# Front_Board_v6.net
KiCad netlist of a schematic drawn in EAGLE
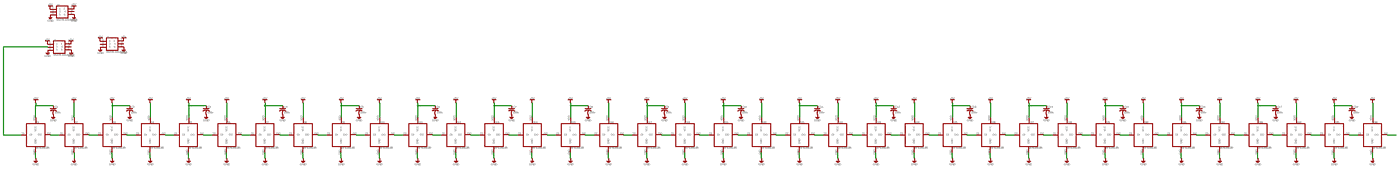
[diagram p0: schematic, sheet 1, overview]
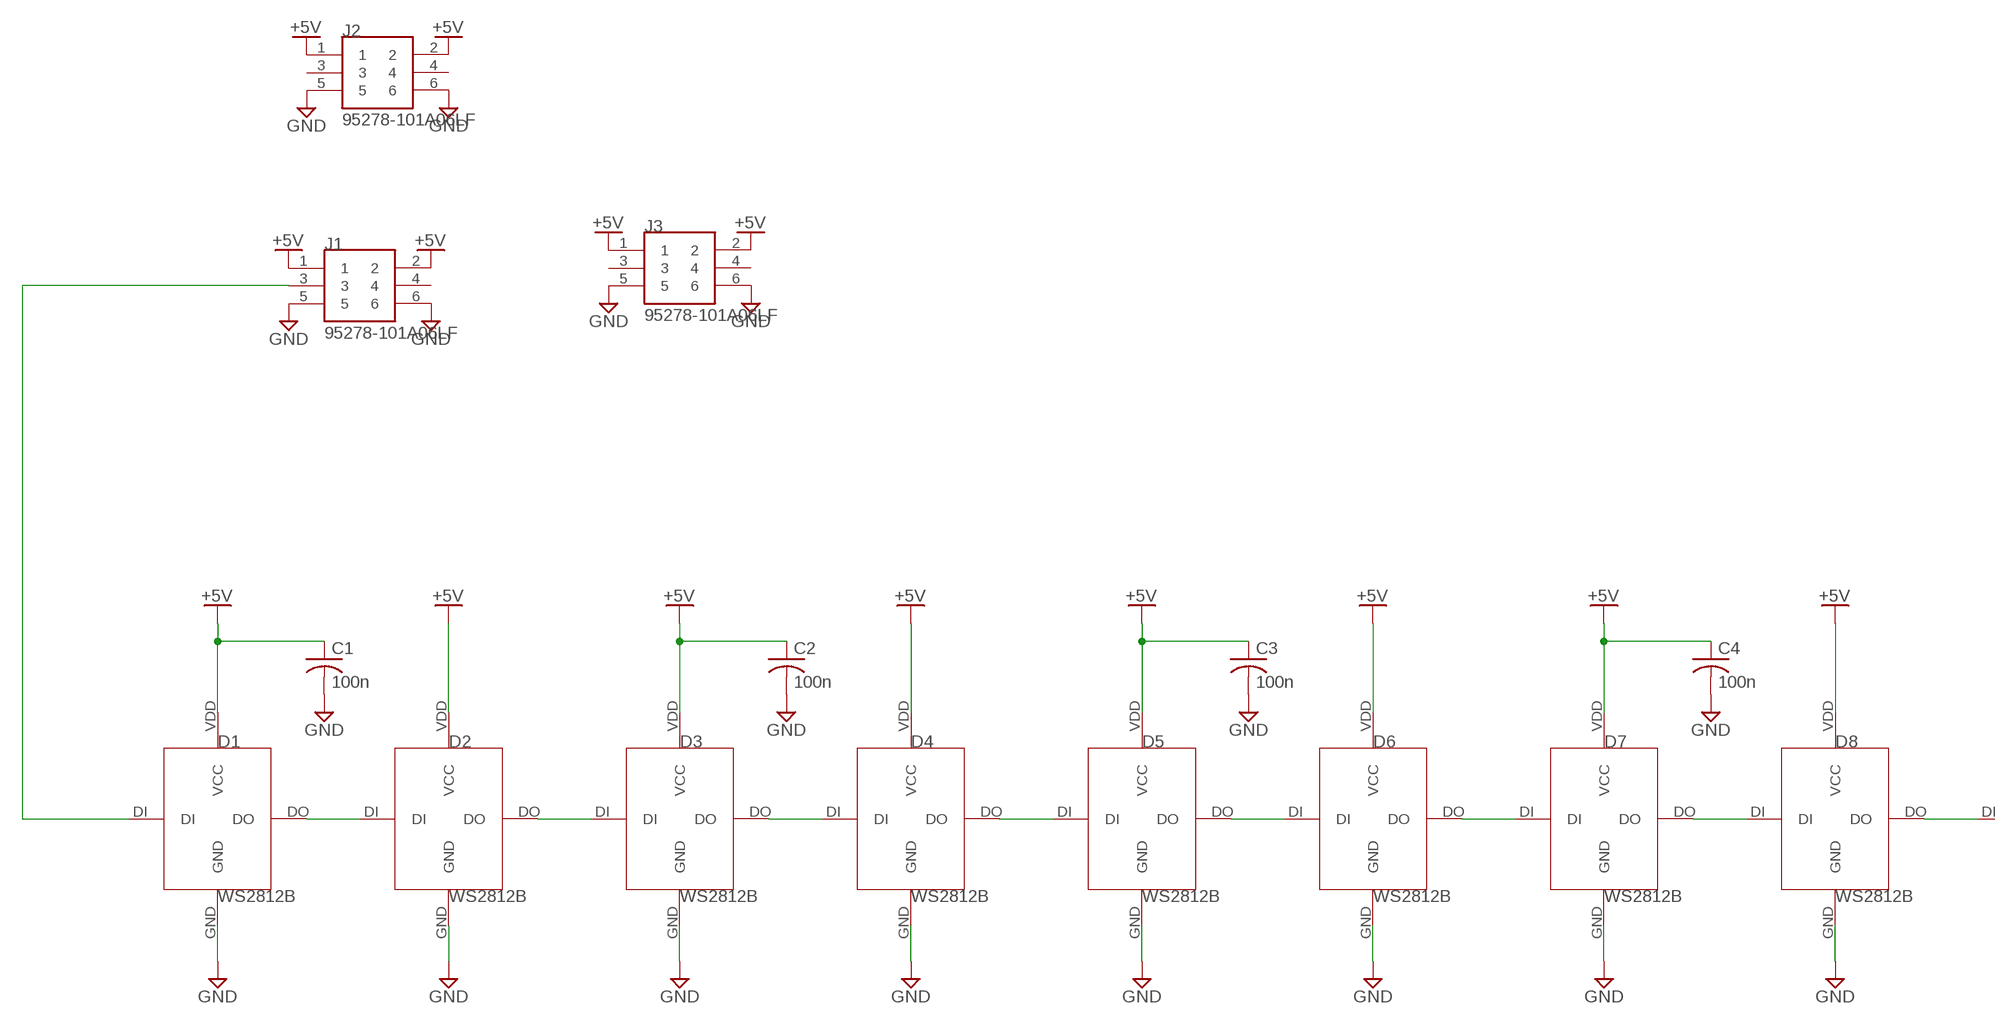
[diagram p1: schematic, sheet 1, part 1 of 4]
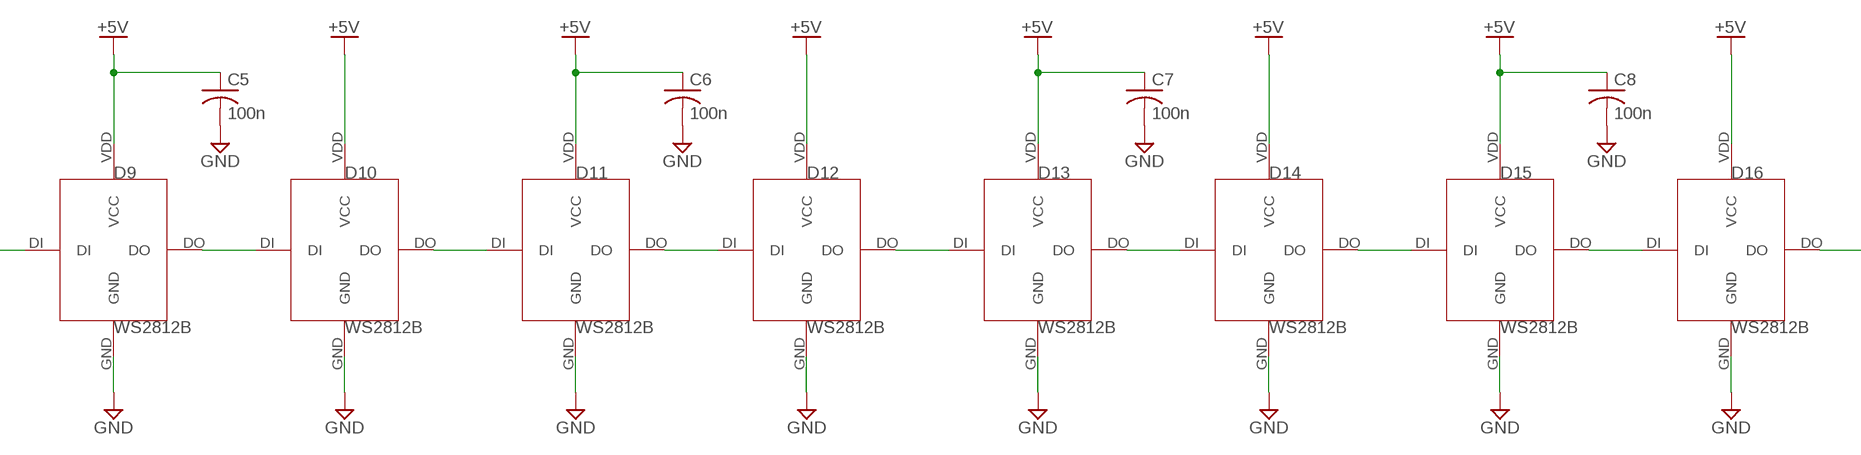
[diagram p2: schematic, sheet 1, part 2 of 4]
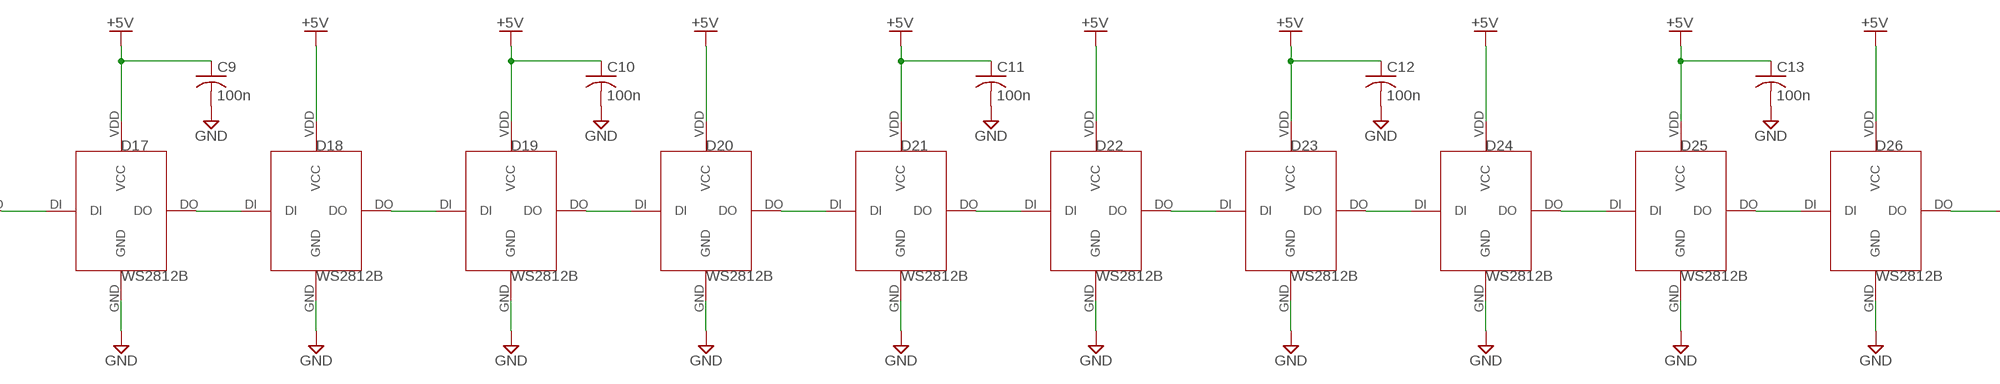
[diagram p3: schematic, sheet 1, part 3 of 4]
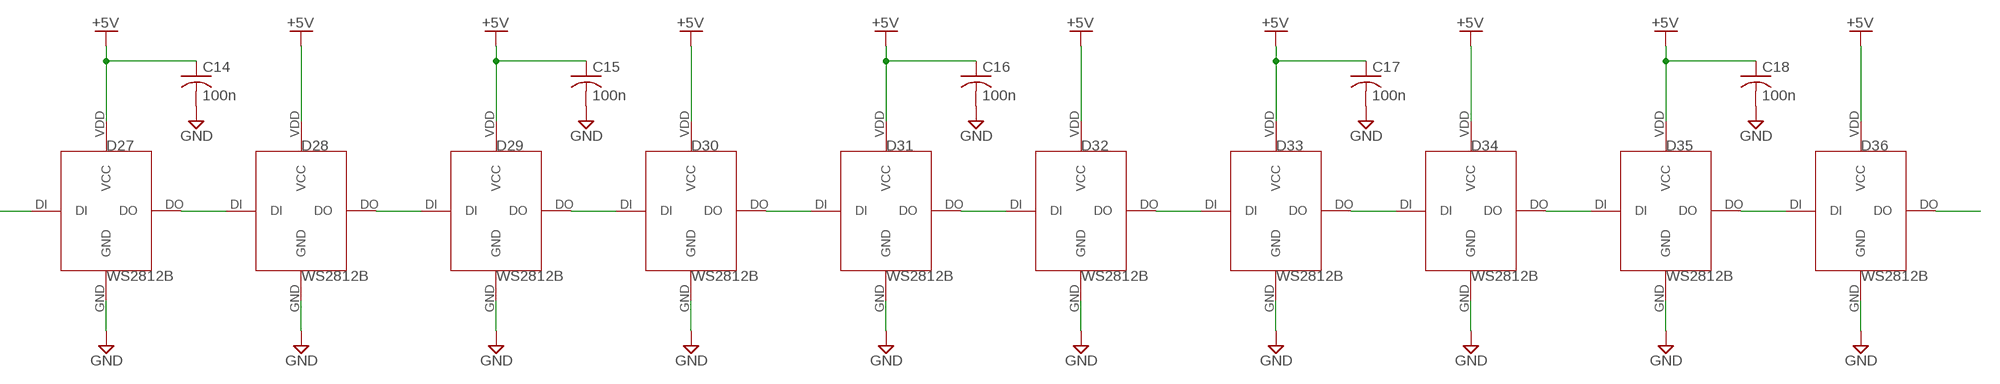
[diagram p4: schematic, sheet 1, part 4 of 4]

(export (version "E")
  (design (tool "Eeschema 10.0.6"))
  (components
    (comp (ref "C1")
      (value "100n")
      (footprint "eagle-import:C0603K")
      (libsource (lib "eagle-import") (part "C-USC0603K"))
    )
    (comp (ref "C2")
      (value "100n")
      (footprint "eagle-import:C0603K")
      (libsource (lib "eagle-import") (part "C-USC0603K"))
    )
    (comp (ref "C3")
      (value "100n")
      (footprint "eagle-import:C0603K")
      (libsource (lib "eagle-import") (part "C-USC0603K"))
    )
    (comp (ref "C4")
      (value "100n")
      (footprint "eagle-import:C0603K")
      (libsource (lib "eagle-import") (part "C-USC0603K"))
    )
    (comp (ref "C5")
      (value "100n")
      (footprint "eagle-import:C0603K")
      (libsource (lib "eagle-import") (part "C-USC0603K"))
    )
    (comp (ref "C6")
      (value "100n")
      (footprint "eagle-import:C0603K")
      (libsource (lib "eagle-import") (part "C-USC0603K"))
    )
    (comp (ref "C7")
      (value "100n")
      (footprint "eagle-import:C0603K")
      (libsource (lib "eagle-import") (part "C-USC0603K"))
    )
    (comp (ref "C8")
      (value "100n")
      (footprint "eagle-import:C0603K")
      (libsource (lib "eagle-import") (part "C-USC0603K"))
    )
    (comp (ref "C9")
      (value "100n")
      (footprint "eagle-import:C0603K")
      (libsource (lib "eagle-import") (part "C-USC0603K"))
    )
    (comp (ref "C10")
      (value "100n")
      (footprint "eagle-import:C0603K")
      (libsource (lib "eagle-import") (part "C-USC0603K"))
    )
    (comp (ref "C11")
      (value "100n")
      (footprint "eagle-import:C0603K")
      (libsource (lib "eagle-import") (part "C-USC0603K"))
    )
    (comp (ref "C12")
      (value "100n")
      (footprint "eagle-import:C0603K")
      (libsource (lib "eagle-import") (part "C-USC0603K"))
    )
    (comp (ref "C13")
      (value "100n")
      (footprint "eagle-import:C0603K")
      (libsource (lib "eagle-import") (part "C-USC0603K"))
    )
    (comp (ref "C14")
      (value "100n")
      (footprint "eagle-import:C0603K")
      (libsource (lib "eagle-import") (part "C-USC0603K"))
    )
    (comp (ref "C15")
      (value "100n")
      (footprint "eagle-import:C0603K")
      (libsource (lib "eagle-import") (part "C-USC0603K"))
    )
    (comp (ref "C16")
      (value "100n")
      (footprint "eagle-import:C0603K")
      (libsource (lib "eagle-import") (part "C-USC0603K"))
    )
    (comp (ref "C17")
      (value "100n")
      (footprint "eagle-import:C0603K")
      (libsource (lib "eagle-import") (part "C-USC0603K"))
    )
    (comp (ref "C18")
      (value "100n")
      (footprint "eagle-import:C0603K")
      (libsource (lib "eagle-import") (part "C-USC0603K"))
    )
    (comp (ref "D1")
      (value "WS2812B")
      (footprint "eagle-import:1010")
      (libsource (lib "eagle-import") (part "WS2812B"))
    )
    (comp (ref "D2")
      (value "WS2812B")
      (footprint "eagle-import:1010")
      (libsource (lib "eagle-import") (part "WS2812B"))
    )
    (comp (ref "D3")
      (value "WS2812B")
      (footprint "eagle-import:1010")
      (libsource (lib "eagle-import") (part "WS2812B"))
    )
    (comp (ref "D4")
      (value "WS2812B")
      (footprint "eagle-import:1010")
      (libsource (lib "eagle-import") (part "WS2812B"))
    )
    (comp (ref "D5")
      (value "WS2812B")
      (footprint "eagle-import:1010")
      (libsource (lib "eagle-import") (part "WS2812B"))
    )
    (comp (ref "D6")
      (value "WS2812B")
      (footprint "eagle-import:1010")
      (libsource (lib "eagle-import") (part "WS2812B"))
    )
    (comp (ref "D7")
      (value "WS2812B")
      (footprint "eagle-import:1010")
      (libsource (lib "eagle-import") (part "WS2812B"))
    )
    (comp (ref "D8")
      (value "WS2812B")
      (footprint "eagle-import:1010")
      (libsource (lib "eagle-import") (part "WS2812B"))
    )
    (comp (ref "D9")
      (value "WS2812B")
      (footprint "eagle-import:1010")
      (libsource (lib "eagle-import") (part "WS2812B"))
    )
    (comp (ref "D10")
      (value "WS2812B")
      (footprint "eagle-import:1010")
      (libsource (lib "eagle-import") (part "WS2812B"))
    )
    (comp (ref "D11")
      (value "WS2812B")
      (footprint "eagle-import:1010")
      (libsource (lib "eagle-import") (part "WS2812B"))
    )
    (comp (ref "D12")
      (value "WS2812B")
      (footprint "eagle-import:1010")
      (libsource (lib "eagle-import") (part "WS2812B"))
    )
    (comp (ref "D13")
      (value "WS2812B")
      (footprint "eagle-import:1010")
      (libsource (lib "eagle-import") (part "WS2812B"))
    )
    (comp (ref "D14")
      (value "WS2812B")
      (footprint "eagle-import:1010")
      (libsource (lib "eagle-import") (part "WS2812B"))
    )
    (comp (ref "D15")
      (value "WS2812B")
      (footprint "eagle-import:1010")
      (libsource (lib "eagle-import") (part "WS2812B"))
    )
    (comp (ref "D16")
      (value "WS2812B")
      (footprint "eagle-import:1010")
      (libsource (lib "eagle-import") (part "WS2812B"))
    )
    (comp (ref "D17")
      (value "WS2812B")
      (footprint "eagle-import:1010")
      (libsource (lib "eagle-import") (part "WS2812B"))
    )
    (comp (ref "D18")
      (value "WS2812B")
      (footprint "eagle-import:1010")
      (libsource (lib "eagle-import") (part "WS2812B"))
    )
    (comp (ref "D19")
      (value "WS2812B")
      (footprint "eagle-import:1010")
      (libsource (lib "eagle-import") (part "WS2812B"))
    )
    (comp (ref "D20")
      (value "WS2812B")
      (footprint "eagle-import:1010")
      (libsource (lib "eagle-import") (part "WS2812B"))
    )
    (comp (ref "D21")
      (value "WS2812B")
      (footprint "eagle-import:1010")
      (libsource (lib "eagle-import") (part "WS2812B"))
    )
    (comp (ref "D22")
      (value "WS2812B")
      (footprint "eagle-import:1010")
      (libsource (lib "eagle-import") (part "WS2812B"))
    )
    (comp (ref "D23")
      (value "WS2812B")
      (footprint "eagle-import:1010")
      (libsource (lib "eagle-import") (part "WS2812B"))
    )
    (comp (ref "D24")
      (value "WS2812B")
      (footprint "eagle-import:1010")
      (libsource (lib "eagle-import") (part "WS2812B"))
    )
    (comp (ref "D25")
      (value "WS2812B")
      (footprint "eagle-import:1010")
      (libsource (lib "eagle-import") (part "WS2812B"))
    )
    (comp (ref "D26")
      (value "WS2812B")
      (footprint "eagle-import:1010")
      (libsource (lib "eagle-import") (part "WS2812B"))
    )
    (comp (ref "D27")
      (value "WS2812B")
      (footprint "eagle-import:1010")
      (libsource (lib "eagle-import") (part "WS2812B"))
    )
    (comp (ref "D28")
      (value "WS2812B")
      (footprint "eagle-import:1010")
      (libsource (lib "eagle-import") (part "WS2812B"))
    )
    (comp (ref "D29")
      (value "WS2812B")
      (footprint "eagle-import:1010")
      (libsource (lib "eagle-import") (part "WS2812B"))
    )
    (comp (ref "D30")
      (value "WS2812B")
      (footprint "eagle-import:1010")
      (libsource (lib "eagle-import") (part "WS2812B"))
    )
    (comp (ref "D31")
      (value "WS2812B")
      (footprint "eagle-import:1010")
      (libsource (lib "eagle-import") (part "WS2812B"))
    )
    (comp (ref "D32")
      (value "WS2812B")
      (footprint "eagle-import:1010")
      (libsource (lib "eagle-import") (part "WS2812B"))
    )
    (comp (ref "D33")
      (value "WS2812B")
      (footprint "eagle-import:1010")
      (libsource (lib "eagle-import") (part "WS2812B"))
    )
    (comp (ref "D34")
      (value "WS2812B")
      (footprint "eagle-import:1010")
      (libsource (lib "eagle-import") (part "WS2812B"))
    )
    (comp (ref "D35")
      (value "WS2812B")
      (footprint "eagle-import:1010")
      (libsource (lib "eagle-import") (part "WS2812B"))
    )
    (comp (ref "D36")
      (value "WS2812B")
      (footprint "eagle-import:1010")
      (libsource (lib "eagle-import") (part "WS2812B"))
    )
    (comp (ref "J1")
      (value "95278-101A06LF")
      (footprint "eagle-import:95278-101A06LF")
      (fields
        (field (name "DIGIKEY_PART_NUMBER") "609-3487-1-ND")
        (field (name "MANUFACTURER") "Amphenol ICC (FCI)")
        (field (name "CREATED_BY") "PCBLayout.com")
      )
      (libsource (lib "eagle-import") (part "95278-101A06LF"))
    )
    (comp (ref "J2")
      (value "95278-101A06LF")
      (footprint "eagle-import:95278-101A06LF")
      (fields
        (field (name "DIGIKEY_PART_NUMBER") "609-3487-1-ND")
        (field (name "MANUFACTURER") "Amphenol ICC (FCI)")
        (field (name "CREATED_BY") "PCBLayout.com")
      )
      (libsource (lib "eagle-import") (part "95278-101A06LF"))
    )
    (comp (ref "J3")
      (value "95278-101A06LF")
      (footprint "eagle-import:95278-101A06LF")
      (fields
        (field (name "DIGIKEY_PART_NUMBER") "609-3487-1-ND")
        (field (name "MANUFACTURER") "Amphenol ICC (FCI)")
        (field (name "CREATED_BY") "PCBLayout.com")
      )
      (libsource (lib "eagle-import") (part "95278-101A06LF"))
    )
  )
  (nets
    (net (code "1") (name "+5V") (class "Default")
      (node (ref "C1") (pin "1") (pinfunction "1_1") (pintype "passive"))
      (node (ref "C10") (pin "1") (pinfunction "1_1") (pintype "passive"))
      (node (ref "C11") (pin "1") (pinfunction "1_1") (pintype "passive"))
      (node (ref "C12") (pin "1") (pinfunction "1_1") (pintype "passive"))
      (node (ref "C13") (pin "1") (pinfunction "1_1") (pintype "passive"))
      (node (ref "C14") (pin "1") (pinfunction "1_1") (pintype "passive"))
      (node (ref "C15") (pin "1") (pinfunction "1_1") (pintype "passive"))
      (node (ref "C16") (pin "1") (pinfunction "1_1") (pintype "passive"))
      (node (ref "C17") (pin "1") (pinfunction "1_1") (pintype "passive"))
      (node (ref "C18") (pin "1") (pinfunction "1_1") (pintype "passive"))
      (node (ref "C2") (pin "1") (pinfunction "1_1") (pintype "passive"))
      (node (ref "C3") (pin "1") (pinfunction "1_1") (pintype "passive"))
      (node (ref "C4") (pin "1") (pinfunction "1_1") (pintype "passive"))
      (node (ref "C5") (pin "1") (pinfunction "1_1") (pintype "passive"))
      (node (ref "C6") (pin "1") (pinfunction "1_1") (pintype "passive"))
      (node (ref "C7") (pin "1") (pinfunction "1_1") (pintype "passive"))
      (node (ref "C8") (pin "1") (pinfunction "1_1") (pintype "passive"))
      (node (ref "C9") (pin "1") (pinfunction "1_1") (pintype "passive"))
      (node (ref "D1") (pin "VDD") (pinfunction "VCC_VDD") (pintype "power_in"))
      (node (ref "D10") (pin "VDD") (pinfunction "VCC_VDD") (pintype "power_in"))
      (node (ref "D11") (pin "VDD") (pinfunction "VCC_VDD") (pintype "power_in"))
      (node (ref "D12") (pin "VDD") (pinfunction "VCC_VDD") (pintype "power_in"))
      (node (ref "D13") (pin "VDD") (pinfunction "VCC_VDD") (pintype "power_in"))
      (node (ref "D14") (pin "VDD") (pinfunction "VCC_VDD") (pintype "power_in"))
      (node (ref "D15") (pin "VDD") (pinfunction "VCC_VDD") (pintype "power_in"))
      (node (ref "D16") (pin "VDD") (pinfunction "VCC_VDD") (pintype "power_in"))
      (node (ref "D17") (pin "VDD") (pinfunction "VCC_VDD") (pintype "power_in"))
      (node (ref "D18") (pin "VDD") (pinfunction "VCC_VDD") (pintype "power_in"))
      (node (ref "D19") (pin "VDD") (pinfunction "VCC_VDD") (pintype "power_in"))
      (node (ref "D2") (pin "VDD") (pinfunction "VCC_VDD") (pintype "power_in"))
      (node (ref "D20") (pin "VDD") (pinfunction "VCC_VDD") (pintype "power_in"))
      (node (ref "D21") (pin "VDD") (pinfunction "VCC_VDD") (pintype "power_in"))
      (node (ref "D22") (pin "VDD") (pinfunction "VCC_VDD") (pintype "power_in"))
      (node (ref "D23") (pin "VDD") (pinfunction "VCC_VDD") (pintype "power_in"))
      (node (ref "D24") (pin "VDD") (pinfunction "VCC_VDD") (pintype "power_in"))
      (node (ref "D25") (pin "VDD") (pinfunction "VCC_VDD") (pintype "power_in"))
      (node (ref "D26") (pin "VDD") (pinfunction "VCC_VDD") (pintype "power_in"))
      (node (ref "D27") (pin "VDD") (pinfunction "VCC_VDD") (pintype "power_in"))
      (node (ref "D28") (pin "VDD") (pinfunction "VCC_VDD") (pintype "power_in"))
      (node (ref "D29") (pin "VDD") (pinfunction "VCC_VDD") (pintype "power_in"))
      (node (ref "D3") (pin "VDD") (pinfunction "VCC_VDD") (pintype "power_in"))
      (node (ref "D30") (pin "VDD") (pinfunction "VCC_VDD") (pintype "power_in"))
      (node (ref "D31") (pin "VDD") (pinfunction "VCC_VDD") (pintype "power_in"))
      (node (ref "D32") (pin "VDD") (pinfunction "VCC_VDD") (pintype "power_in"))
      (node (ref "D33") (pin "VDD") (pinfunction "VCC_VDD") (pintype "power_in"))
      (node (ref "D34") (pin "VDD") (pinfunction "VCC_VDD") (pintype "power_in"))
      (node (ref "D35") (pin "VDD") (pinfunction "VCC_VDD") (pintype "power_in"))
      (node (ref "D36") (pin "VDD") (pinfunction "VCC_VDD") (pintype "power_in"))
      (node (ref "D4") (pin "VDD") (pinfunction "VCC_VDD") (pintype "power_in"))
      (node (ref "D5") (pin "VDD") (pinfunction "VCC_VDD") (pintype "power_in"))
      (node (ref "D6") (pin "VDD") (pinfunction "VCC_VDD") (pintype "power_in"))
      (node (ref "D7") (pin "VDD") (pinfunction "VCC_VDD") (pintype "power_in"))
      (node (ref "D8") (pin "VDD") (pinfunction "VCC_VDD") (pintype "power_in"))
      (node (ref "D9") (pin "VDD") (pinfunction "VCC_VDD") (pintype "power_in"))
      (node (ref "J1") (pin "1") (pinfunction "1_1") (pintype "passive"))
      (node (ref "J1") (pin "2") (pinfunction "2_2") (pintype "passive"))
      (node (ref "J2") (pin "1") (pinfunction "1_1") (pintype "passive"))
      (node (ref "J2") (pin "2") (pinfunction "2_2") (pintype "passive"))
      (node (ref "J3") (pin "1") (pinfunction "1_1") (pintype "passive"))
      (node (ref "J3") (pin "2") (pinfunction "2_2") (pintype "passive"))
    )
    (net (code "2") (name "GND") (class "Default")
      (node (ref "C1") (pin "2") (pinfunction "2_2") (pintype "passive"))
      (node (ref "C10") (pin "2") (pinfunction "2_2") (pintype "passive"))
      (node (ref "C11") (pin "2") (pinfunction "2_2") (pintype "passive"))
      (node (ref "C12") (pin "2") (pinfunction "2_2") (pintype "passive"))
      (node (ref "C13") (pin "2") (pinfunction "2_2") (pintype "passive"))
      (node (ref "C14") (pin "2") (pinfunction "2_2") (pintype "passive"))
      (node (ref "C15") (pin "2") (pinfunction "2_2") (pintype "passive"))
      (node (ref "C16") (pin "2") (pinfunction "2_2") (pintype "passive"))
      (node (ref "C17") (pin "2") (pinfunction "2_2") (pintype "passive"))
      (node (ref "C18") (pin "2") (pinfunction "2_2") (pintype "passive"))
      (node (ref "C2") (pin "2") (pinfunction "2_2") (pintype "passive"))
      (node (ref "C3") (pin "2") (pinfunction "2_2") (pintype "passive"))
      (node (ref "C4") (pin "2") (pinfunction "2_2") (pintype "passive"))
      (node (ref "C5") (pin "2") (pinfunction "2_2") (pintype "passive"))
      (node (ref "C6") (pin "2") (pinfunction "2_2") (pintype "passive"))
      (node (ref "C7") (pin "2") (pinfunction "2_2") (pintype "passive"))
      (node (ref "C8") (pin "2") (pinfunction "2_2") (pintype "passive"))
      (node (ref "C9") (pin "2") (pinfunction "2_2") (pintype "passive"))
      (node (ref "D1") (pin "GND") (pinfunction "GND_GND") (pintype "power_in"))
      (node (ref "D10") (pin "GND") (pinfunction "GND_GND") (pintype "power_in"))
      (node (ref "D11") (pin "GND") (pinfunction "GND_GND") (pintype "power_in"))
      (node (ref "D12") (pin "GND") (pinfunction "GND_GND") (pintype "power_in"))
      (node (ref "D13") (pin "GND") (pinfunction "GND_GND") (pintype "power_in"))
      (node (ref "D14") (pin "GND") (pinfunction "GND_GND") (pintype "power_in"))
      (node (ref "D15") (pin "GND") (pinfunction "GND_GND") (pintype "power_in"))
      (node (ref "D16") (pin "GND") (pinfunction "GND_GND") (pintype "power_in"))
      (node (ref "D17") (pin "GND") (pinfunction "GND_GND") (pintype "power_in"))
      (node (ref "D18") (pin "GND") (pinfunction "GND_GND") (pintype "power_in"))
      (node (ref "D19") (pin "GND") (pinfunction "GND_GND") (pintype "power_in"))
      (node (ref "D2") (pin "GND") (pinfunction "GND_GND") (pintype "power_in"))
      (node (ref "D20") (pin "GND") (pinfunction "GND_GND") (pintype "power_in"))
      (node (ref "D21") (pin "GND") (pinfunction "GND_GND") (pintype "power_in"))
      (node (ref "D22") (pin "GND") (pinfunction "GND_GND") (pintype "power_in"))
      (node (ref "D23") (pin "GND") (pinfunction "GND_GND") (pintype "power_in"))
      (node (ref "D24") (pin "GND") (pinfunction "GND_GND") (pintype "power_in"))
      (node (ref "D25") (pin "GND") (pinfunction "GND_GND") (pintype "power_in"))
      (node (ref "D26") (pin "GND") (pinfunction "GND_GND") (pintype "power_in"))
      (node (ref "D27") (pin "GND") (pinfunction "GND_GND") (pintype "power_in"))
      (node (ref "D28") (pin "GND") (pinfunction "GND_GND") (pintype "power_in"))
      (node (ref "D29") (pin "GND") (pinfunction "GND_GND") (pintype "power_in"))
      (node (ref "D3") (pin "GND") (pinfunction "GND_GND") (pintype "power_in"))
      (node (ref "D30") (pin "GND") (pinfunction "GND_GND") (pintype "power_in"))
      (node (ref "D31") (pin "GND") (pinfunction "GND_GND") (pintype "power_in"))
      (node (ref "D32") (pin "GND") (pinfunction "GND_GND") (pintype "power_in"))
      (node (ref "D33") (pin "GND") (pinfunction "GND_GND") (pintype "power_in"))
      (node (ref "D34") (pin "GND") (pinfunction "GND_GND") (pintype "power_in"))
      (node (ref "D35") (pin "GND") (pinfunction "GND_GND") (pintype "power_in"))
      (node (ref "D36") (pin "GND") (pinfunction "GND_GND") (pintype "power_in"))
      (node (ref "D4") (pin "GND") (pinfunction "GND_GND") (pintype "power_in"))
      (node (ref "D5") (pin "GND") (pinfunction "GND_GND") (pintype "power_in"))
      (node (ref "D6") (pin "GND") (pinfunction "GND_GND") (pintype "power_in"))
      (node (ref "D7") (pin "GND") (pinfunction "GND_GND") (pintype "power_in"))
      (node (ref "D8") (pin "GND") (pinfunction "GND_GND") (pintype "power_in"))
      (node (ref "D9") (pin "GND") (pinfunction "GND_GND") (pintype "power_in"))
      (node (ref "J1") (pin "5") (pinfunction "5_5") (pintype "passive"))
      (node (ref "J1") (pin "6") (pinfunction "6_6") (pintype "passive"))
      (node (ref "J2") (pin "5") (pinfunction "5_5") (pintype "passive"))
      (node (ref "J2") (pin "6") (pinfunction "6_6") (pintype "passive"))
      (node (ref "J3") (pin "5") (pinfunction "5_5") (pintype "passive"))
      (node (ref "J3") (pin "6") (pinfunction "6_6") (pintype "passive"))
    )
    (net (code "3") (name "Net-(D1-PadDI)") (class "Default")
      (node (ref "D1") (pin "DI") (pinfunction "DI_DI") (pintype "input"))
      (node (ref "J1") (pin "3") (pinfunction "3_3") (pintype "passive"))
    )
    (net (code "4") (name "Net-(D1-PadDO)") (class "Default")
      (node (ref "D1") (pin "DO") (pinfunction "DO_DO") (pintype "output"))
      (node (ref "D2") (pin "DI") (pinfunction "DI_DI") (pintype "input"))
    )
    (net (code "5") (name "Net-(D2-PadDO)") (class "Default")
      (node (ref "D2") (pin "DO") (pinfunction "DO_DO") (pintype "output"))
      (node (ref "D3") (pin "DI") (pinfunction "DI_DI") (pintype "input"))
    )
    (net (code "6") (name "Net-(D3-PadDO)") (class "Default")
      (node (ref "D3") (pin "DO") (pinfunction "DO_DO") (pintype "output"))
      (node (ref "D4") (pin "DI") (pinfunction "DI_DI") (pintype "input"))
    )
    (net (code "7") (name "Net-(D4-PadDO)") (class "Default")
      (node (ref "D4") (pin "DO") (pinfunction "DO_DO") (pintype "output"))
      (node (ref "D5") (pin "DI") (pinfunction "DI_DI") (pintype "input"))
    )
    (net (code "8") (name "Net-(D5-PadDO)") (class "Default")
      (node (ref "D5") (pin "DO") (pinfunction "DO_DO") (pintype "output"))
      (node (ref "D6") (pin "DI") (pinfunction "DI_DI") (pintype "input"))
    )
    (net (code "9") (name "Net-(D6-PadDO)") (class "Default")
      (node (ref "D6") (pin "DO") (pinfunction "DO_DO") (pintype "output"))
      (node (ref "D7") (pin "DI") (pinfunction "DI_DI") (pintype "input"))
    )
    (net (code "10") (name "Net-(D7-PadDO)") (class "Default")
      (node (ref "D7") (pin "DO") (pinfunction "DO_DO") (pintype "output"))
      (node (ref "D8") (pin "DI") (pinfunction "DI_DI") (pintype "input"))
    )
    (net (code "11") (name "Net-(D8-PadDO)") (class "Default")
      (node (ref "D8") (pin "DO") (pinfunction "DO_DO") (pintype "output"))
      (node (ref "D9") (pin "DI") (pinfunction "DI_DI") (pintype "input"))
    )
    (net (code "12") (name "Net-(D10-PadDI)") (class "Default")
      (node (ref "D10") (pin "DI") (pinfunction "DI_DI") (pintype "input"))
      (node (ref "D9") (pin "DO") (pinfunction "DO_DO") (pintype "output"))
    )
    (net (code "13") (name "Net-(D10-PadDO)") (class "Default")
      (node (ref "D10") (pin "DO") (pinfunction "DO_DO") (pintype "output"))
      (node (ref "D11") (pin "DI") (pinfunction "DI_DI") (pintype "input"))
    )
    (net (code "14") (name "Net-(D11-PadDO)") (class "Default")
      (node (ref "D11") (pin "DO") (pinfunction "DO_DO") (pintype "output"))
      (node (ref "D12") (pin "DI") (pinfunction "DI_DI") (pintype "input"))
    )
    (net (code "15") (name "Net-(D12-PadDO)") (class "Default")
      (node (ref "D12") (pin "DO") (pinfunction "DO_DO") (pintype "output"))
      (node (ref "D13") (pin "DI") (pinfunction "DI_DI") (pintype "input"))
    )
    (net (code "16") (name "Net-(D13-PadDO)") (class "Default")
      (node (ref "D13") (pin "DO") (pinfunction "DO_DO") (pintype "output"))
      (node (ref "D14") (pin "DI") (pinfunction "DI_DI") (pintype "input"))
    )
    (net (code "17") (name "Net-(D14-PadDO)") (class "Default")
      (node (ref "D14") (pin "DO") (pinfunction "DO_DO") (pintype "output"))
      (node (ref "D15") (pin "DI") (pinfunction "DI_DI") (pintype "input"))
    )
    (net (code "18") (name "Net-(D15-PadDO)") (class "Default")
      (node (ref "D15") (pin "DO") (pinfunction "DO_DO") (pintype "output"))
      (node (ref "D16") (pin "DI") (pinfunction "DI_DI") (pintype "input"))
    )
    (net (code "19") (name "Net-(D16-PadDO)") (class "Default")
      (node (ref "D16") (pin "DO") (pinfunction "DO_DO") (pintype "output"))
      (node (ref "D17") (pin "DI") (pinfunction "DI_DI") (pintype "input"))
    )
    (net (code "20") (name "Net-(D17-PadDO)") (class "Default")
      (node (ref "D17") (pin "DO") (pinfunction "DO_DO") (pintype "output"))
      (node (ref "D18") (pin "DI") (pinfunction "DI_DI") (pintype "input"))
    )
    (net (code "21") (name "Net-(D18-PadDO)") (class "Default")
      (node (ref "D18") (pin "DO") (pinfunction "DO_DO") (pintype "output"))
      (node (ref "D19") (pin "DI") (pinfunction "DI_DI") (pintype "input"))
    )
    (net (code "22") (name "Net-(D19-PadDO)") (class "Default")
      (node (ref "D19") (pin "DO") (pinfunction "DO_DO") (pintype "output"))
      (node (ref "D20") (pin "DI") (pinfunction "DI_DI") (pintype "input"))
    )
    (net (code "23") (name "Net-(D20-PadDO)") (class "Default")
      (node (ref "D20") (pin "DO") (pinfunction "DO_DO") (pintype "output"))
      (node (ref "D21") (pin "DI") (pinfunction "DI_DI") (pintype "input"))
    )
    (net (code "24") (name "Net-(D21-PadDO)") (class "Default")
      (node (ref "D21") (pin "DO") (pinfunction "DO_DO") (pintype "output"))
      (node (ref "D22") (pin "DI") (pinfunction "DI_DI") (pintype "input"))
    )
    (net (code "25") (name "Net-(D22-PadDO)") (class "Default")
      (node (ref "D22") (pin "DO") (pinfunction "DO_DO") (pintype "output"))
      (node (ref "D23") (pin "DI") (pinfunction "DI_DI") (pintype "input"))
    )
    (net (code "26") (name "Net-(D23-PadDO)") (class "Default")
      (node (ref "D23") (pin "DO") (pinfunction "DO_DO") (pintype "output"))
      (node (ref "D24") (pin "DI") (pinfunction "DI_DI") (pintype "input"))
    )
    (net (code "27") (name "Net-(D24-PadDO)") (class "Default")
      (node (ref "D24") (pin "DO") (pinfunction "DO_DO") (pintype "output"))
      (node (ref "D25") (pin "DI") (pinfunction "DI_DI") (pintype "input"))
    )
    (net (code "28") (name "Net-(D25-PadDO)") (class "Default")
      (node (ref "D25") (pin "DO") (pinfunction "DO_DO") (pintype "output"))
      (node (ref "D26") (pin "DI") (pinfunction "DI_DI") (pintype "input"))
    )
    (net (code "29") (name "Net-(D26-PadDO)") (class "Default")
      (node (ref "D26") (pin "DO") (pinfunction "DO_DO") (pintype "output"))
      (node (ref "D27") (pin "DI") (pinfunction "DI_DI") (pintype "input"))
    )
    (net (code "30") (name "Net-(D27-PadDO)") (class "Default")
      (node (ref "D27") (pin "DO") (pinfunction "DO_DO") (pintype "output"))
      (node (ref "D28") (pin "DI") (pinfunction "DI_DI") (pintype "input"))
    )
    (net (code "31") (name "Net-(D28-PadDO)") (class "Default")
      (node (ref "D28") (pin "DO") (pinfunction "DO_DO") (pintype "output"))
      (node (ref "D29") (pin "DI") (pinfunction "DI_DI") (pintype "input"))
    )
    (net (code "32") (name "Net-(D29-PadDO)") (class "Default")
      (node (ref "D29") (pin "DO") (pinfunction "DO_DO") (pintype "output"))
      (node (ref "D30") (pin "DI") (pinfunction "DI_DI") (pintype "input"))
    )
    (net (code "33") (name "Net-(D30-PadDO)") (class "Default")
      (node (ref "D30") (pin "DO") (pinfunction "DO_DO") (pintype "output"))
      (node (ref "D31") (pin "DI") (pinfunction "DI_DI") (pintype "input"))
    )
    (net (code "34") (name "Net-(D31-PadDO)") (class "Default")
      (node (ref "D31") (pin "DO") (pinfunction "DO_DO") (pintype "output"))
      (node (ref "D32") (pin "DI") (pinfunction "DI_DI") (pintype "input"))
    )
    (net (code "35") (name "Net-(D32-PadDO)") (class "Default")
      (node (ref "D32") (pin "DO") (pinfunction "DO_DO") (pintype "output"))
      (node (ref "D33") (pin "DI") (pinfunction "DI_DI") (pintype "input"))
    )
    (net (code "36") (name "Net-(D33-PadDO)") (class "Default")
      (node (ref "D33") (pin "DO") (pinfunction "DO_DO") (pintype "output"))
      (node (ref "D34") (pin "DI") (pinfunction "DI_DI") (pintype "input"))
    )
    (net (code "37") (name "Net-(D34-PadDO)") (class "Default")
      (node (ref "D34") (pin "DO") (pinfunction "DO_DO") (pintype "output"))
      (node (ref "D35") (pin "DI") (pinfunction "DI_DI") (pintype "input"))
    )
    (net (code "38") (name "Net-(D35-PadDO)") (class "Default")
      (node (ref "D35") (pin "DO") (pinfunction "DO_DO") (pintype "output"))
      (node (ref "D36") (pin "DI") (pinfunction "DI_DI") (pintype "input"))
    )
    (net (code "39") (name "unconnected-(D36-PadDO)") (class "Default")
      (node (ref "D36") (pin "DO") (pinfunction "DO_DO") (pintype "output"))
    )
    (net (code "40") (name "unconnected-(J1-Pad4)") (class "Default")
      (node (ref "J1") (pin "4") (pinfunction "4_4") (pintype "passive"))
    )
    (net (code "41") (name "unconnected-(J2-Pad3)") (class "Default")
      (node (ref "J2") (pin "3") (pinfunction "3_3") (pintype "passive"))
    )
    (net (code "42") (name "unconnected-(J2-Pad4)") (class "Default")
      (node (ref "J2") (pin "4") (pinfunction "4_4") (pintype "passive"))
    )
    (net (code "43") (name "unconnected-(J3-Pad3)") (class "Default")
      (node (ref "J3") (pin "3") (pinfunction "3_3") (pintype "passive"))
    )
    (net (code "44") (name "unconnected-(J3-Pad4)") (class "Default")
      (node (ref "J3") (pin "4") (pinfunction "4_4") (pintype "passive"))
    )
  )
)
